# WL_144.net
KiCad netlist of a schematic drawn in Altium Designer
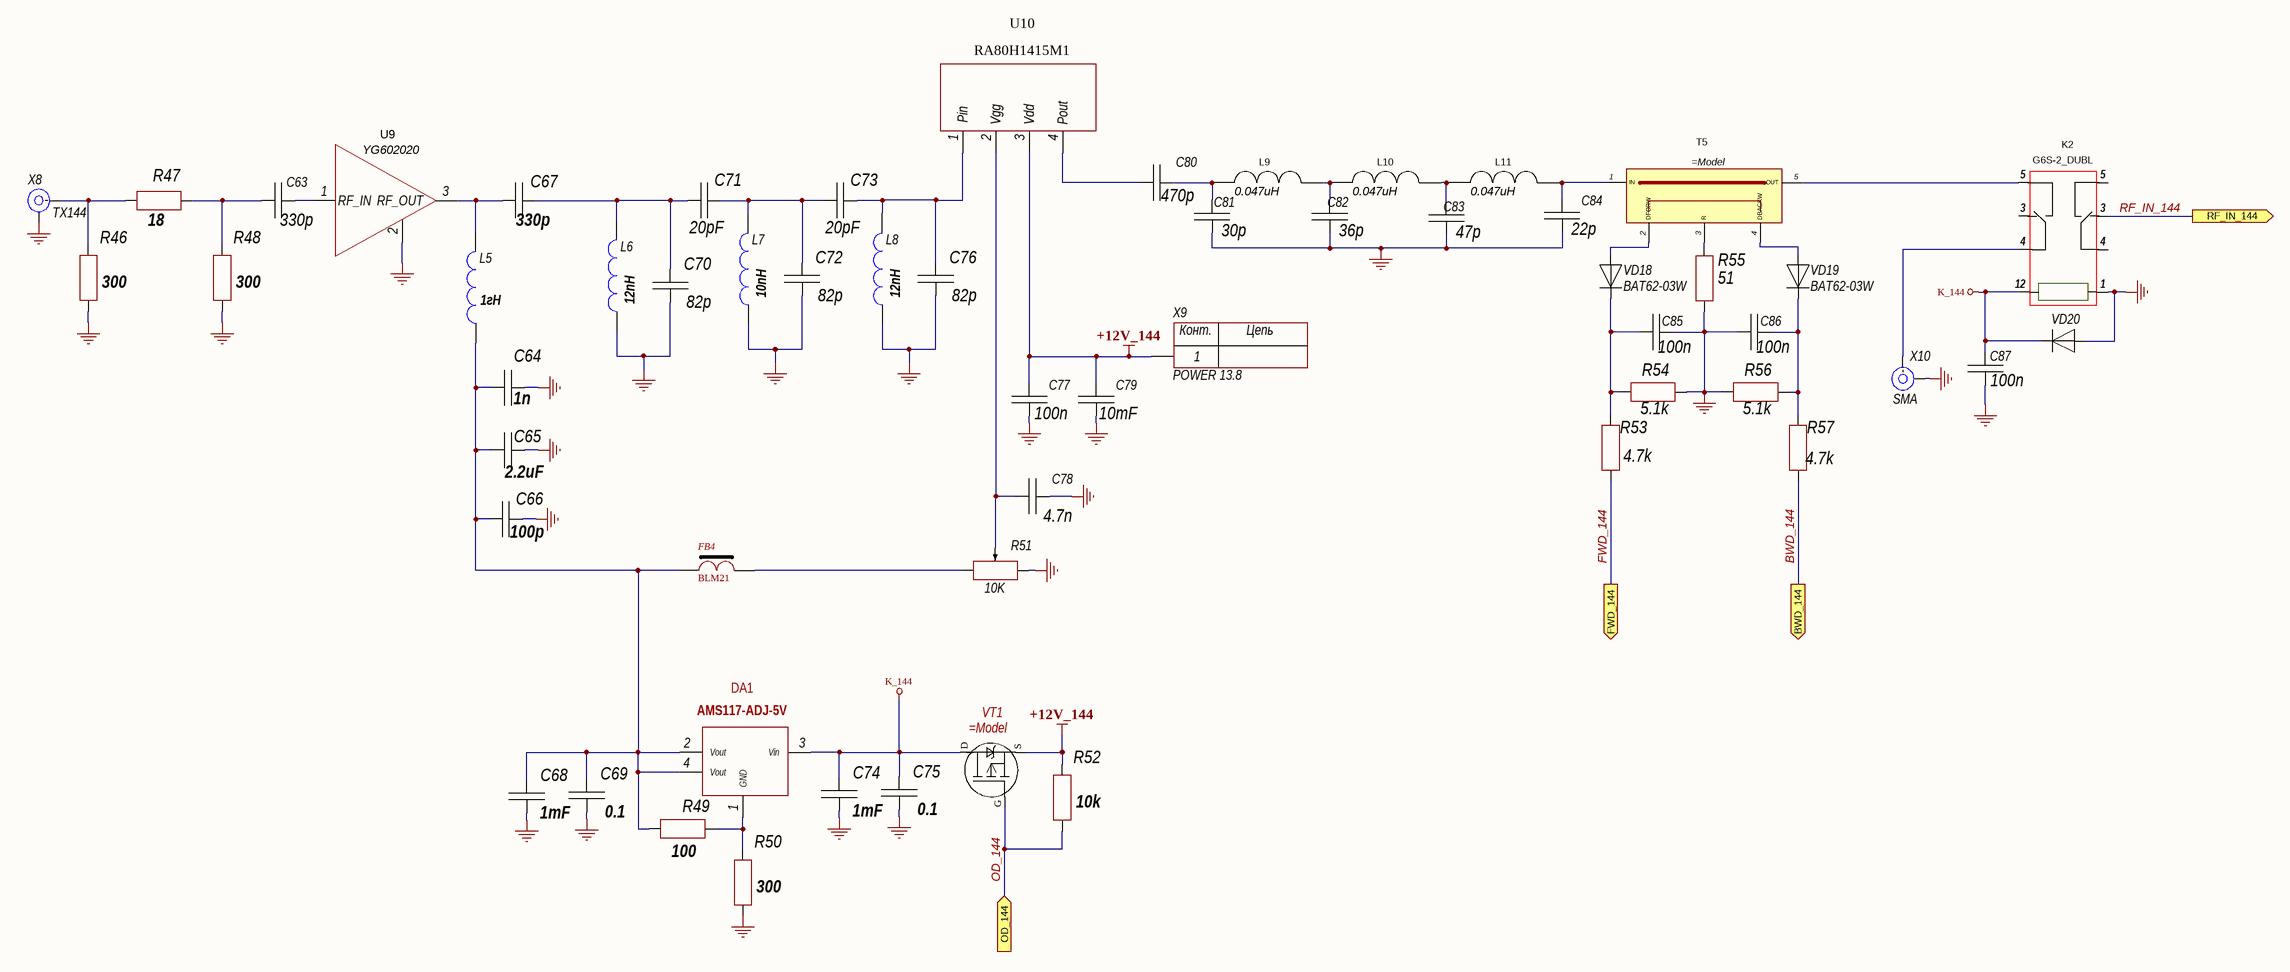
[diagram p0: WL_144.SchDoc]

(export (version "E")
  (design (tool "Eeschema 10.0.6"))
  (components
    (comp (ref "C63")
      (value "330p")
      (footprint "standard:CH0805C")
      (libsource (lib "Discrete") (part "Capacitor"))
    )
    (comp (ref "C64")
      (value "1n")
      (footprint "standard:CH0805C")
      (libsource (lib "Discrete") (part "Capacitor"))
    )
    (comp (ref "C65")
      (value "2.2uF")
      (footprint "standard:CH0805C")
      (libsource (lib "") (part "Capacitor_1"))
    )
    (comp (ref "C66")
      (value "100p")
      (footprint "standard:CH0805C")
      (libsource (lib "Discrete") (part "Capacitor"))
    )
    (comp (ref "C67")
      (value "330p")
      (footprint "standard:CH0805C")
      (libsource (lib "Discrete") (part "Capacitor"))
    )
    (comp (ref "C68")
      (value "1mF")
      (footprint "standard:CH0805C")
      (libsource (lib "Discrete") (part "Capacitor"))
    )
    (comp (ref "C69")
      (value "0.1")
      (footprint "standard:CH0805C")
      (libsource (lib "Discrete") (part "Capacitor"))
    )
    (comp (ref "C70")
      (value "82p")
      (footprint "standard:CH0805C")
      (libsource (lib "Discrete") (part "Capacitor"))
    )
    (comp (ref "C71")
      (value "20pF")
      (footprint "standard:CH0805C")
      (libsource (lib "Discrete") (part "Capacitor"))
    )
    (comp (ref "C72")
      (value "82p")
      (footprint "standard:CH0805C")
      (libsource (lib "Discrete") (part "Capacitor"))
    )
    (comp (ref "C73")
      (value "20pF")
      (footprint "standard:CH0805C")
      (libsource (lib "Discrete") (part "Capacitor"))
    )
    (comp (ref "C74")
      (value "1mF")
      (footprint "standard:CH0805C")
      (libsource (lib "Discrete") (part "Capacitor"))
    )
    (comp (ref "C75")
      (value "0.1")
      (footprint "standard:CH0805C")
      (libsource (lib "Discrete") (part "Capacitor"))
    )
    (comp (ref "C76")
      (value "82p")
      (footprint "standard:CH0805C")
      (libsource (lib "Discrete") (part "Capacitor"))
    )
    (comp (ref "C77")
      (value "100n")
      (footprint "standard:CH1206C")
      (libsource (lib "Discrete") (part "Capacitor"))
    )
    (comp (ref "C78")
      (value "4.7n")
      (footprint "standard:CH0805C")
      (libsource (lib "Discrete") (part "Capacitor"))
    )
    (comp (ref "C79")
      (value "10mF")
      (footprint "standard:CH1206C")
      (libsource (lib "Discrete") (part "Capacitor"))
    )
    (comp (ref "C80")
      (value "470p")
      (footprint "standard:CH1206C")
      (libsource (lib "Discrete") (part "Capacitor"))
    )
    (comp (ref "C81")
      (value "30p")
      (footprint "standard:CH1206C")
      (libsource (lib "Discrete") (part "Capacitor"))
    )
    (comp (ref "C82")
      (value "36p")
      (footprint "standard:CH1206C")
      (libsource (lib "Discrete") (part "Capacitor"))
    )
    (comp (ref "C83")
      (value "47p")
      (footprint "standard:CH1206C")
      (libsource (lib "Discrete") (part "Capacitor"))
    )
    (comp (ref "C84")
      (value "22p")
      (footprint "standard:CH1206C")
      (libsource (lib "Discrete") (part "Capacitor"))
    )
    (comp (ref "C85")
      (value "100n")
      (footprint "standard:CH0805C")
      (libsource (lib "Discrete") (part "Capacitor"))
    )
    (comp (ref "C86")
      (value "100n")
      (footprint "standard:CH0805C")
      (libsource (lib "Discrete") (part "Capacitor"))
    )
    (comp (ref "C87")
      (value "100n")
      (footprint "standard:CH0805C")
      (libsource (lib "Discrete") (part "Capacitor"))
    )
    (comp (ref "DA1") (value "AMS117-ADJ-5V") (footprint "SOT223") (libsource (lib "Analog") (part "AMS117")))
    (comp (ref "FB4") (value "BLM21") (footprint "CH0805L") (libsource (lib "Discrete") (part "FB-1")))
    (comp (ref "K2")
      (value "G6S-2_DUBL")
      (footprint "G6S-2_DUBL")
      (libsource (lib "Relay") (part "G6S-2_DUBL"))
    )
    (comp (ref "L5")
      (value "1гH")
      (footprint "katuhka")
      (libsource (lib "Transformers") (part "Inductor ring"))
    )
    (comp (ref "L6")
      (value "12nH")
      (footprint "katuhka")
      (libsource (lib "Transformers") (part "Inductor ring"))
    )
    (comp (ref "L7")
      (value "10nH")
      (footprint "katuhka")
      (libsource (lib "Transformers") (part "Inductor ring"))
    )
    (comp (ref "L8")
      (value "12nH")
      (footprint "katuhka")
      (libsource (lib "Transformers") (part "Inductor ring"))
    )
    (comp (ref "L9")
      (value "0.047uH")
      (footprint "L-FNC_V3")
      (libsource (lib "Transformers") (part "TRANS-1"))
    )
    (comp (ref "L10")
      (value "0.047uH")
      (footprint "L-FNC_V3")
      (libsource (lib "Transformers") (part "TRANS-1"))
    )
    (comp (ref "L11")
      (value "0.047uH")
      (footprint "L-FNC_V3")
      (libsource (lib "Transformers") (part "TRANS-1"))
    )
    (comp (ref "R46")
      (value "300")
      (footprint "standard:CH0805R")
      (libsource (lib "Discrete") (part "Resistor"))
    )
    (comp (ref "R47") (value "18") (footprint "standard:CH0805R") (libsource (lib "") (part "Resistor_1")))
    (comp (ref "R48")
      (value "300")
      (footprint "standard:CH0805R")
      (libsource (lib "Discrete") (part "Resistor"))
    )
    (comp (ref "R49") (value "100") (footprint "standard:CH0805R") (libsource (lib "") (part "Resistor_1")))
    (comp (ref "R50")
      (value "300")
      (footprint "standard:CH0805R")
      (libsource (lib "Discrete") (part "Resistor"))
    )
    (comp (ref "R51")
      (value "10K")
      (footprint "custom:RES: 3296W")
      (libsource (lib "Discrete") (part "ADJ resistor"))
    )
    (comp (ref "R52")
      (value "10k")
      (footprint "standard:CH0805R")
      (libsource (lib "Discrete") (part "Resistor"))
    )
    (comp (ref "R53") (value "4.7k") (footprint "standard:CH0805R") (libsource (lib "") (part "Resistor_2")))
    (comp (ref "R54") (value "5.1k") (footprint "standard:CH0805R") (libsource (lib "") (part "Resistor_1")))
    (comp (ref "R55")
      (value "51")
      (footprint "standard:CH1206R")
      (libsource (lib "Discrete") (part "Resistor"))
    )
    (comp (ref "R56") (value "5.1k") (footprint "standard:CH0805R") (libsource (lib "") (part "Resistor_1")))
    (comp (ref "R57") (value "4.7k") (footprint "standard:CH0805R") (libsource (lib "") (part "Resistor_2")))
    (comp (ref "T5") (value "~") (footprint "SWR_D") (libsource (lib "Transformers") (part "VHF_KSV1")))
    (comp (ref "U9") (value "YG602020") (footprint "SOT89_123") (libsource (lib "Digital") (part "YG602020")))
    (comp (ref "U10")
      (value "RA80H1415M1")
      (footprint "RA80H1415M1 - duplicate")
      (libsource (lib "Digital") (part "RA80H1415M1"))
    )
    (comp (ref "VD18") (value "BAT62-03W") (footprint "1N4148") (libsource (lib "Diods") (part "Diod")))
    (comp (ref "VD19") (value "BAT62-03W") (footprint "1N4148") (libsource (lib "Diods") (part "Diod")))
    (comp (ref "VD20") (value "~") (footprint "1N4148") (libsource (lib "Diods") (part "Diod")))
    (comp (ref "VT1") (value "~") (footprint "SOT23_132") (libsource (lib "Transistor") (part "P-KANAL")))
    (comp (ref "X8")
      (value "TX144")
      (footprint "CON: u.Fl")
      (description "RF")
      (libsource (lib "Connectors") (part "SMA"))
    )
    (comp (ref "X9")
      (value "POWER 13.8")
      (footprint "CON: KNIFE_5MM")
      (libsource (lib "Connectors") (part "1-Connector"))
    )
    (comp (ref "X10")
      (value "SMA")
      (footprint "custom:CON: SMA")
      (description "RF")
      (libsource (lib "Connectors") (part "SMA"))
    )
  )
  (nets
    (net (code "1") (name "+12V_144") (class "Default")
      (node (ref "C77") (pin "2") (pinfunction "2_2") (pintype "power_in"))
      (node (ref "C79") (pin "2") (pinfunction "2_2") (pintype "power_in"))
      (node (ref "R52") (pin "2") (pinfunction "2_2") (pintype "passive"))
      (node (ref "U10") (pin "3") (pinfunction "Vdd_3") (pintype "passive"))
      (node (ref "VT1") (pin "2") (pinfunction "Исток_2") (pintype "passive"))
      (node (ref "X9") (pin "1") (pinfunction "1_1") (pintype "passive"))
    )
    (net (code "2") (name "/BWD_144") (class "Default")
      (node (ref "R57") (pin "2") (pinfunction "2_2") (pintype "passive"))
    )
    (net (code "3") (name "/FWD_144") (class "Default")
      (node (ref "R53") (pin "2") (pinfunction "2_2") (pintype "passive"))
    )
    (net (code "4") (name "/OD_144") (class "Default")
      (node (ref "R52") (pin "1") (pinfunction "1_1") (pintype "passive"))
      (node (ref "VT1") (pin "1") (pinfunction "Затвор(Gate)_1") (pintype "passive"))
    )
    (net (code "5") (name "/RF_IN_144") (class "Default")
      (node (ref "K2") (pin "3") (pinfunction "3_3") (pintype "passive"))
    )
    (net (code "6") (name "GND") (class "Default")
      (node (ref "C64") (pin "2") (pinfunction "2_2") (pintype "power_in"))
      (node (ref "C65") (pin "2") (pinfunction "2_2") (pintype "power_in"))
      (node (ref "C66") (pin "2") (pinfunction "2_2") (pintype "power_in"))
      (node (ref "C68") (pin "1") (pinfunction "1_1") (pintype "power_in"))
      (node (ref "C69") (pin "1") (pinfunction "1_1") (pintype "power_in"))
      (node (ref "C70") (pin "1") (pinfunction "1_1") (pintype "power_in"))
      (node (ref "C72") (pin "1") (pinfunction "1_1") (pintype "power_in"))
      (node (ref "C74") (pin "1") (pinfunction "1_1") (pintype "power_in"))
      (node (ref "C75") (pin "1") (pinfunction "1_1") (pintype "power_in"))
      (node (ref "C76") (pin "1") (pinfunction "1_1") (pintype "power_in"))
      (node (ref "C77") (pin "1") (pinfunction "1_1") (pintype "power_in"))
      (node (ref "C78") (pin "1") (pinfunction "1_1") (pintype "power_in"))
      (node (ref "C79") (pin "1") (pinfunction "1_1") (pintype "power_in"))
      (node (ref "C81") (pin "1") (pinfunction "1_1") (pintype "power_in"))
      (node (ref "C82") (pin "1") (pinfunction "1_1") (pintype "power_in"))
      (node (ref "C83") (pin "1") (pinfunction "1_1") (pintype "power_in"))
      (node (ref "C84") (pin "1") (pinfunction "1_1") (pintype "power_in"))
      (node (ref "C85") (pin "1") (pinfunction "1_1") (pintype "power_in"))
      (node (ref "C86") (pin "2") (pinfunction "2_2") (pintype "power_in"))
      (node (ref "C87") (pin "2") (pinfunction "2_2") (pintype "power_in"))
      (node (ref "K2") (pin "1") (pinfunction "1_1") (pintype "passive"))
      (node (ref "L6") (pin "2") (pinfunction "2_2") (pintype "passive"))
      (node (ref "L7") (pin "2") (pinfunction "2_2") (pintype "passive"))
      (node (ref "L8") (pin "2") (pinfunction "2_2") (pintype "passive"))
      (node (ref "R46") (pin "1") (pinfunction "1_1") (pintype "passive"))
      (node (ref "R48") (pin "1") (pinfunction "1_1") (pintype "passive"))
      (node (ref "R50") (pin "1") (pinfunction "1_1") (pintype "passive"))
      (node (ref "R51") (pin "3") (pinfunction "3_3") (pintype "passive"))
      (node (ref "R54") (pin "1") (pinfunction "1_1") (pintype "passive"))
      (node (ref "R55") (pin "1") (pinfunction "1_1") (pintype "passive"))
      (node (ref "R56") (pin "2") (pinfunction "2_2") (pintype "passive"))
      (node (ref "U9") (pin "2") (pinfunction "GND_2") (pintype "passive"))
      (node (ref "VD20") (pin "1") (pinfunction "1_1") (pintype "passive"))
      (node (ref "X10") (pin "2") (pinfunction "IN_2") (pintype "passive"))
      (node (ref "X8") (pin "2") (pinfunction "IN_2") (pintype "passive"))
    )
    (net (code "7") (name "K_144") (class "Default")
      (node (ref "C74") (pin "2") (pinfunction "2_2") (pintype "power_in"))
      (node (ref "C75") (pin "2") (pinfunction "2_2") (pintype "power_in"))
      (node (ref "C87") (pin "1") (pinfunction "1_1") (pintype "power_in"))
      (node (ref "DA1") (pin "3") (pinfunction "Vin_3") (pintype "passive"))
      (node (ref "K2") (pin "12") (pinfunction "12_12") (pintype "passive"))
      (node (ref "VD20") (pin "2") (pinfunction "2_2") (pintype "passive"))
      (node (ref "VT1") (pin "3") (pinfunction "Сток_3") (pintype "passive"))
    )
    (net (code "8") (name "Net-(C63-Pad2)") (class "Default")
      (node (ref "C63") (pin "2") (pinfunction "2_2") (pintype "power_in"))
      (node (ref "R47") (pin "1") (pinfunction "1_1") (pintype "passive"))
      (node (ref "R48") (pin "2") (pinfunction "2_2") (pintype "passive"))
    )
    (net (code "9") (name "Net-(C64-Pad1)") (class "Default")
      (node (ref "C64") (pin "1") (pinfunction "1_1") (pintype "power_in"))
      (node (ref "C65") (pin "1") (pinfunction "1_1") (pintype "power_in"))
      (node (ref "C66") (pin "1") (pinfunction "1_1") (pintype "power_in"))
      (node (ref "C68") (pin "2") (pinfunction "2_2") (pintype "power_in"))
      (node (ref "C69") (pin "2") (pinfunction "2_2") (pintype "power_in"))
      (node (ref "DA1") (pin "2") (pinfunction "Vout_2") (pintype "passive"))
      (node (ref "DA1") (pin "4") (pinfunction "Vout_4") (pintype "passive"))
      (node (ref "FB4") (pin "1") (pinfunction "1_1") (pintype "passive"))
      (node (ref "L5") (pin "2") (pinfunction "2_2") (pintype "passive"))
      (node (ref "R49") (pin "2") (pinfunction "2_2") (pintype "passive"))
    )
    (net (code "10") (name "Net-(C67-Pad2)") (class "Default")
      (node (ref "C67") (pin "2") (pinfunction "2_2") (pintype "power_in"))
      (node (ref "C70") (pin "2") (pinfunction "2_2") (pintype "power_in"))
      (node (ref "C71") (pin "1") (pinfunction "1_1") (pintype "power_in"))
      (node (ref "L6") (pin "1") (pinfunction "1_1") (pintype "passive"))
    )
    (net (code "11") (name "Net-(C71-Pad2)") (class "Default")
      (node (ref "C71") (pin "2") (pinfunction "2_2") (pintype "power_in"))
      (node (ref "C72") (pin "2") (pinfunction "2_2") (pintype "power_in"))
      (node (ref "C73") (pin "1") (pinfunction "1_1") (pintype "power_in"))
      (node (ref "L7") (pin "1") (pinfunction "1_1") (pintype "passive"))
    )
    (net (code "12") (name "Net-(C80-Pad1)") (class "Default")
      (node (ref "C80") (pin "1") (pinfunction "1_1") (pintype "power_in"))
      (node (ref "C81") (pin "2") (pinfunction "2_2") (pintype "power_in"))
      (node (ref "L9") (pin "1") (pinfunction "1_1") (pintype "power_in"))
    )
    (net (code "13") (name "Net-(C82-Pad2)") (class "Default")
      (node (ref "C82") (pin "2") (pinfunction "2_2") (pintype "power_in"))
      (node (ref "L10") (pin "1") (pinfunction "1_1") (pintype "power_in"))
      (node (ref "L9") (pin "2") (pinfunction "2_2") (pintype "power_in"))
    )
    (net (code "14") (name "Net-(C83-Pad2)") (class "Default")
      (node (ref "C83") (pin "2") (pinfunction "2_2") (pintype "power_in"))
      (node (ref "L10") (pin "2") (pinfunction "2_2") (pintype "power_in"))
      (node (ref "L11") (pin "1") (pinfunction "1_1") (pintype "power_in"))
    )
    (net (code "15") (name "Net-(C85-Pad2)") (class "Default")
      (node (ref "C85") (pin "2") (pinfunction "2_2") (pintype "power_in"))
      (node (ref "R53") (pin "1") (pinfunction "1_1") (pintype "passive"))
      (node (ref "R54") (pin "2") (pinfunction "2_2") (pintype "passive"))
      (node (ref "VD18") (pin "2") (pinfunction "2_2") (pintype "passive"))
    )
    (net (code "16") (name "Net-(C86-Pad1)") (class "Default")
      (node (ref "C86") (pin "1") (pinfunction "1_1") (pintype "power_in"))
      (node (ref "R56") (pin "1") (pinfunction "1_1") (pintype "passive"))
      (node (ref "R57") (pin "1") (pinfunction "1_1") (pintype "passive"))
      (node (ref "VD19") (pin "2") (pinfunction "2_2") (pintype "passive"))
    )
    (net (code "17") (name "Net-(DA1-GND)") (class "Default")
      (node (ref "DA1") (pin "1") (pinfunction "GND_1") (pintype "passive"))
      (node (ref "R49") (pin "1") (pinfunction "1_1") (pintype "passive"))
      (node (ref "R50") (pin "2") (pinfunction "2_2") (pintype "passive"))
    )
    (net (code "18") (name "Net-(FB4-Pad2)") (class "Default")
      (node (ref "FB4") (pin "2") (pinfunction "2_2") (pintype "passive"))
      (node (ref "R51") (pin "1") (pinfunction "1_1") (pintype "passive"))
    )
    (net (code "19") (name "Net-(K2-Pad4)_1") (class "Default")
      (node (ref "K2") (pin "4") (pinfunction "4_4") (pintype "passive"))
      (node (ref "X10") (pin "1") (pinfunction "IN_1") (pintype "passive"))
    )
    (net (code "20") (name "Net-(R46-Pad2)") (class "Default")
      (node (ref "R46") (pin "2") (pinfunction "2_2") (pintype "passive"))
      (node (ref "R47") (pin "2") (pinfunction "2_2") (pintype "passive"))
      (node (ref "X8") (pin "1") (pinfunction "IN_1") (pintype "passive"))
    )
    (net (code "21") (name "Net-(T5-DBACKW)") (class "Default")
      (node (ref "T5") (pin "4") (pinfunction "DBACKW_4") (pintype "passive"))
      (node (ref "VD19") (pin "1") (pinfunction "1_1") (pintype "passive"))
    )
    (net (code "22") (name "Net-(T5-DFORW)") (class "Default")
      (node (ref "T5") (pin "2") (pinfunction "DFORW_2") (pintype "passive"))
      (node (ref "VD18") (pin "1") (pinfunction "1_1") (pintype "passive"))
    )
    (net (code "23") (name "Net-(T5-IN)") (class "Default")
      (node (ref "C84") (pin "2") (pinfunction "2_2") (pintype "power_in"))
      (node (ref "L11") (pin "2") (pinfunction "2_2") (pintype "power_in"))
      (node (ref "T5") (pin "1") (pinfunction "IN_1") (pintype "passive"))
    )
    (net (code "24") (name "Net-(T5-OUT)") (class "Default")
      (node (ref "K2") (pin "5") (pinfunction "5_5") (pintype "passive"))
      (node (ref "T5") (pin "5") (pinfunction "OUT_5") (pintype "passive"))
    )
    (net (code "25") (name "Net-(T5-R)") (class "Default")
      (node (ref "R55") (pin "2") (pinfunction "2_2") (pintype "passive"))
      (node (ref "T5") (pin "3") (pinfunction "R_3") (pintype "passive"))
    )
    (net (code "26") (name "Net-(U9-RF_IN)") (class "Default")
      (node (ref "C63") (pin "1") (pinfunction "1_1") (pintype "power_in"))
      (node (ref "U9") (pin "1") (pinfunction "RF_IN_1") (pintype "passive"))
    )
    (net (code "27") (name "Net-(U9-RF_OUT)") (class "Default")
      (node (ref "C67") (pin "1") (pinfunction "1_1") (pintype "power_in"))
      (node (ref "L5") (pin "1") (pinfunction "1_1") (pintype "passive"))
      (node (ref "U9") (pin "3") (pinfunction "RF_OUT_3") (pintype "passive"))
    )
    (net (code "28") (name "Net-(U10-Pin)") (class "Default")
      (node (ref "C73") (pin "2") (pinfunction "2_2") (pintype "power_in"))
      (node (ref "C76") (pin "2") (pinfunction "2_2") (pintype "power_in"))
      (node (ref "L8") (pin "1") (pinfunction "1_1") (pintype "passive"))
      (node (ref "U10") (pin "1") (pinfunction "Pin_1") (pintype "passive"))
    )
    (net (code "29") (name "Net-(U10-Pout)") (class "Default")
      (node (ref "C80") (pin "2") (pinfunction "2_2") (pintype "power_in"))
      (node (ref "U10") (pin "4") (pinfunction "Pout_4") (pintype "passive"))
    )
    (net (code "30") (name "Net-(U10-Vgg)") (class "Default")
      (node (ref "C78") (pin "2") (pinfunction "2_2") (pintype "power_in"))
      (node (ref "R51") (pin "2") (pinfunction "2_2") (pintype "passive"))
      (node (ref "U10") (pin "2") (pinfunction "Vgg_2") (pintype "passive"))
    )
    (net (code "31") (name "unconnected-(K2-Pad3)") (class "Default")
      (node (ref "K2") (pin "3") (pinfunction "3_3") (pintype "passive"))
    )
    (net (code "32") (name "unconnected-(K2-Pad4)") (class "Default")
      (node (ref "K2") (pin "4") (pinfunction "4_4") (pintype "passive"))
    )
    (net (code "33") (name "unconnected-(K2-Pad5)") (class "Default")
      (node (ref "K2") (pin "5") (pinfunction "5_5") (pintype "passive"))
    )
  )
)
